# demo3.net
KiCad netlist of a schematic drawn in EAGLE
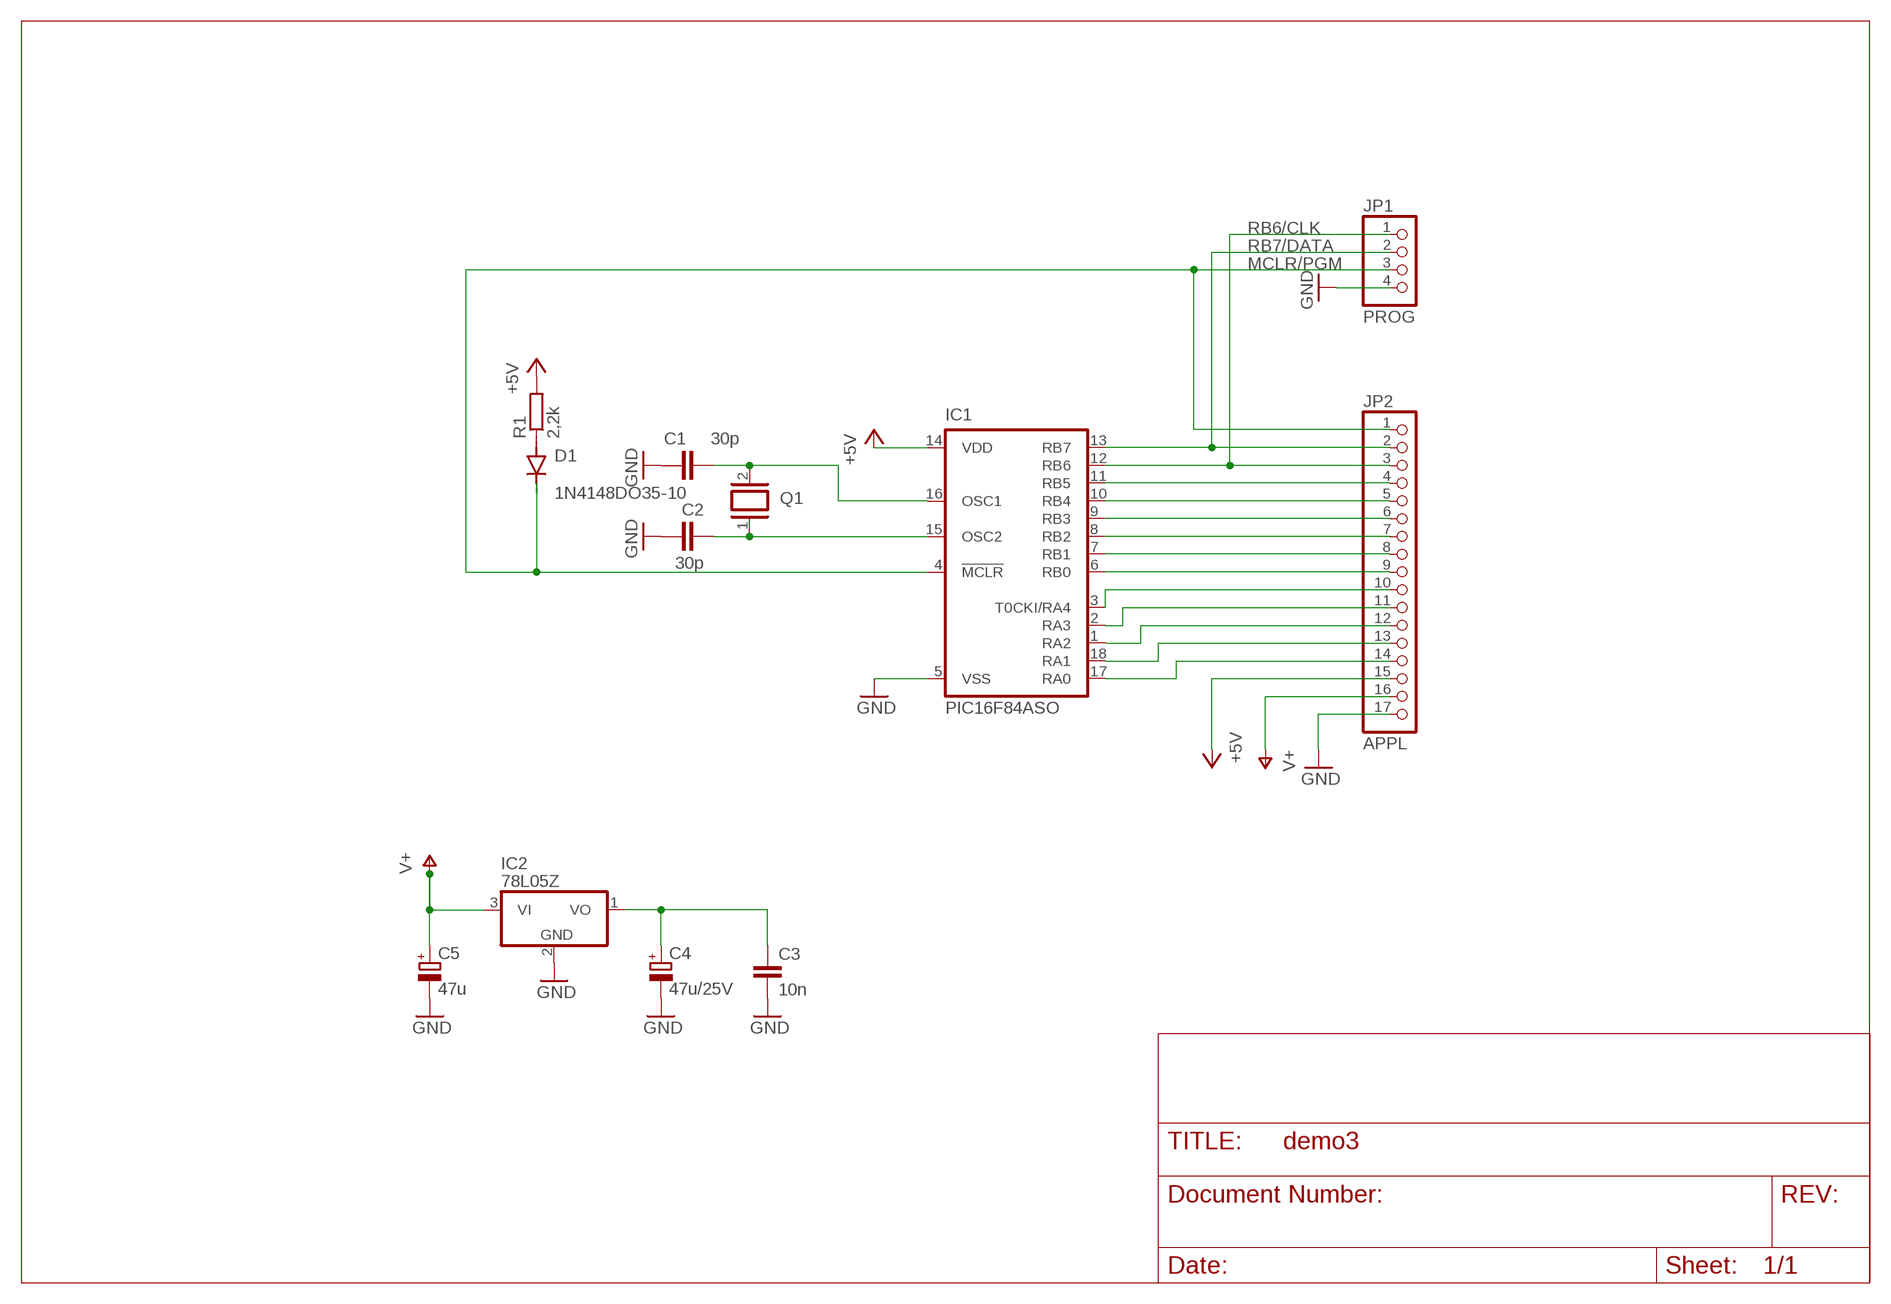
[diagram p0: schematic, sheet 1]

(export (version "E")
  (design (tool "Eeschema 10.0.6"))
  (components
    (comp (ref "C1")
      (value "30p")
      (footprint "eagle-import:C1206")
      (libsource (lib "eagle-import") (part "C-EUC1206"))
    )
    (comp (ref "C2")
      (value "30p")
      (footprint "eagle-import:C1206")
      (libsource (lib "eagle-import") (part "C-EUC1206"))
    )
    (comp (ref "C3")
      (value "10n")
      (footprint "eagle-import:C025-025X050")
      (libsource (lib "eagle-import") (part "C-EU025-025X050"))
    )
    (comp (ref "C4")
      (value "47u/25V")
      (footprint "eagle-import:TAP5-45")
      (libsource (lib "eagle-import") (part "CPOL-EUTAP5-45"))
    )
    (comp (ref "C5")
      (value "47u")
      (footprint "eagle-import:TAP5-45")
      (libsource (lib "eagle-import") (part "CPOL-EUTAP5-45"))
    )
    (comp (ref "D1")
      (value "1N4148DO35-10")
      (footprint "eagle-import:DO35-10")
      (libsource (lib "eagle-import") (part "1N4148DO35-10"))
    )
    (comp (ref "IC1")
      (value "PIC16F84ASO")
      (footprint "eagle-import:SO-18W")
      (fields (field (name "MF") "MICROCHIP") (field (name "MPN") "PIC16F84A-04/SO"))
      (libsource (lib "eagle-import") (part "PIC16F8SO4A"))
    )
    (comp (ref "IC2")
      (value "78L05Z")
      (footprint "eagle-import:TO92")
      (libsource (lib "eagle-import") (part "78ZL05"))
    )
    (comp (ref "JP1")
      (value "PROG")
      (footprint "eagle-import:1X04")
      (libsource (lib "eagle-import") (part "PINHD-1X4"))
    )
    (comp (ref "JP2")
      (value "APPL")
      (footprint "eagle-import:1X17")
      (libsource (lib "eagle-import") (part "PINHD-1X17"))
    )
    (comp (ref "Q1")
      (value "XTAL/S")
      (footprint "eagle-import:QS")
      (libsource (lib "eagle-import") (part "XTAL/S"))
    )
    (comp (ref "R1")
      (value "2,2k")
      (footprint "eagle-import:R1206")
      (libsource (lib "eagle-import") (part "R-EU_R1206"))
    )
  )
  (nets
    (net (code "1") (name "+5V") (class "Default")
      (node (ref "IC1") (pin "14") (pinfunction "VDD_14") (pintype "power_in"))
      (node (ref "JP2") (pin "15") (pinfunction "15_15") (pintype "passive"))
      (node (ref "R1") (pin "2") (pinfunction "2_2") (pintype "passive"))
    )
    (net (code "2") (name "/MCLR{slash}PGM") (class "Default")
      (node (ref "D1") (pin "C") (pinfunction "C_C") (pintype "passive"))
      (node (ref "IC1") (pin "4") (pinfunction "~{MCLR}_4") (pintype "input"))
      (node (ref "JP1") (pin "3") (pinfunction "3_3") (pintype "passive"))
      (node (ref "JP2") (pin "1") (pinfunction "1_1") (pintype "passive"))
    )
    (net (code "3") (name "/RB6{slash}CLK") (class "Default")
      (node (ref "IC1") (pin "12") (pinfunction "RB6_12") (pintype "bidirectional"))
      (node (ref "JP1") (pin "1") (pinfunction "1_1") (pintype "passive"))
      (node (ref "JP2") (pin "3") (pinfunction "3_3") (pintype "passive"))
    )
    (net (code "4") (name "/RB7{slash}DATA") (class "Default")
      (node (ref "IC1") (pin "13") (pinfunction "RB7_13") (pintype "bidirectional"))
      (node (ref "JP1") (pin "2") (pinfunction "2_2") (pintype "passive"))
      (node (ref "JP2") (pin "2") (pinfunction "2_2") (pintype "passive"))
    )
    (net (code "5") (name "GND") (class "Default")
      (node (ref "C1") (pin "1") (pinfunction "1_1") (pintype "passive"))
      (node (ref "C2") (pin "1") (pinfunction "1_1") (pintype "passive"))
      (node (ref "C3") (pin "2") (pinfunction "2_2") (pintype "passive"))
      (node (ref "C4") (pin "-") (pinfunction "-_-") (pintype "passive"))
      (node (ref "C5") (pin "-") (pinfunction "-_-") (pintype "passive"))
      (node (ref "IC1") (pin "5") (pinfunction "VSS_5") (pintype "power_in"))
      (node (ref "IC2") (pin "2") (pinfunction "GND_2") (pintype "passive"))
      (node (ref "JP1") (pin "4") (pinfunction "4_4") (pintype "passive"))
      (node (ref "JP2") (pin "17") (pinfunction "17_17") (pintype "passive"))
    )
    (net (code "6") (name "Net-(D1-PadA)") (class "Default")
      (node (ref "D1") (pin "A") (pinfunction "A_A") (pintype "passive"))
      (node (ref "R1") (pin "1") (pinfunction "1_1") (pintype "passive"))
    )
    (net (code "7") (name "Net-(IC1-OSC1)") (class "Default")
      (node (ref "C1") (pin "2") (pinfunction "2_2") (pintype "passive"))
      (node (ref "IC1") (pin "16") (pinfunction "OSC1_16") (pintype "input"))
      (node (ref "Q1") (pin "2") (pinfunction "2_2") (pintype "passive"))
    )
    (net (code "8") (name "Net-(IC1-OSC2)") (class "Default")
      (node (ref "C2") (pin "2") (pinfunction "2_2") (pintype "passive"))
      (node (ref "IC1") (pin "15") (pinfunction "OSC2_15") (pintype "output"))
      (node (ref "Q1") (pin "1") (pinfunction "1_1") (pintype "passive"))
    )
    (net (code "9") (name "Net-(IC1-RA0)") (class "Default")
      (node (ref "IC1") (pin "17") (pinfunction "RA0_17") (pintype "bidirectional"))
      (node (ref "JP2") (pin "14") (pinfunction "14_14") (pintype "passive"))
    )
    (net (code "10") (name "Net-(IC1-RA1)") (class "Default")
      (node (ref "IC1") (pin "18") (pinfunction "RA1_18") (pintype "bidirectional"))
      (node (ref "JP2") (pin "13") (pinfunction "13_13") (pintype "passive"))
    )
    (net (code "11") (name "Net-(IC1-RA2)") (class "Default")
      (node (ref "IC1") (pin "1") (pinfunction "RA2_1") (pintype "bidirectional"))
      (node (ref "JP2") (pin "12") (pinfunction "12_12") (pintype "passive"))
    )
    (net (code "12") (name "Net-(IC1-RA3)") (class "Default")
      (node (ref "IC1") (pin "2") (pinfunction "RA3_2") (pintype "bidirectional"))
      (node (ref "JP2") (pin "11") (pinfunction "11_11") (pintype "passive"))
    )
    (net (code "13") (name "Net-(IC1-RB0)") (class "Default")
      (node (ref "IC1") (pin "6") (pinfunction "RB0_6") (pintype "bidirectional"))
      (node (ref "JP2") (pin "9") (pinfunction "9_9") (pintype "passive"))
    )
    (net (code "14") (name "Net-(IC1-RB1)") (class "Default")
      (node (ref "IC1") (pin "7") (pinfunction "RB1_7") (pintype "bidirectional"))
      (node (ref "JP2") (pin "8") (pinfunction "8_8") (pintype "passive"))
    )
    (net (code "15") (name "Net-(IC1-RB2)") (class "Default")
      (node (ref "IC1") (pin "8") (pinfunction "RB2_8") (pintype "bidirectional"))
      (node (ref "JP2") (pin "7") (pinfunction "7_7") (pintype "passive"))
    )
    (net (code "16") (name "Net-(IC1-RB3)") (class "Default")
      (node (ref "IC1") (pin "9") (pinfunction "RB3_9") (pintype "bidirectional"))
      (node (ref "JP2") (pin "6") (pinfunction "6_6") (pintype "passive"))
    )
    (net (code "17") (name "Net-(IC1-RB4)") (class "Default")
      (node (ref "IC1") (pin "10") (pinfunction "RB4_10") (pintype "bidirectional"))
      (node (ref "JP2") (pin "5") (pinfunction "5_5") (pintype "passive"))
    )
    (net (code "18") (name "Net-(IC1-RB5)") (class "Default")
      (node (ref "IC1") (pin "11") (pinfunction "RB5_11") (pintype "bidirectional"))
      (node (ref "JP2") (pin "4") (pinfunction "4_4") (pintype "passive"))
    )
    (net (code "19") (name "Net-(IC1-T0CKI{slash}RA4)") (class "Default")
      (node (ref "IC1") (pin "3") (pinfunction "T0CKI/RA4_3") (pintype "bidirectional"))
      (node (ref "JP2") (pin "10") (pinfunction "10_10") (pintype "passive"))
    )
    (net (code "20") (name "Net-(IC2-VO)") (class "Default")
      (node (ref "C3") (pin "1") (pinfunction "1_1") (pintype "passive"))
      (node (ref "C4") (pin "+") (pinfunction "+_+") (pintype "passive"))
      (node (ref "IC2") (pin "1") (pinfunction "VO_1") (pintype "passive"))
    )
    (net (code "21") (name "V+") (class "Default")
      (node (ref "C5") (pin "+") (pinfunction "+_+") (pintype "passive"))
      (node (ref "IC2") (pin "3") (pinfunction "VI_3") (pintype "input"))
      (node (ref "JP2") (pin "16") (pinfunction "16_16") (pintype "passive"))
    )
  )
)
